# Elektroskate_Teensy_20141205.net
KiCad netlist of a schematic drawn in EAGLE
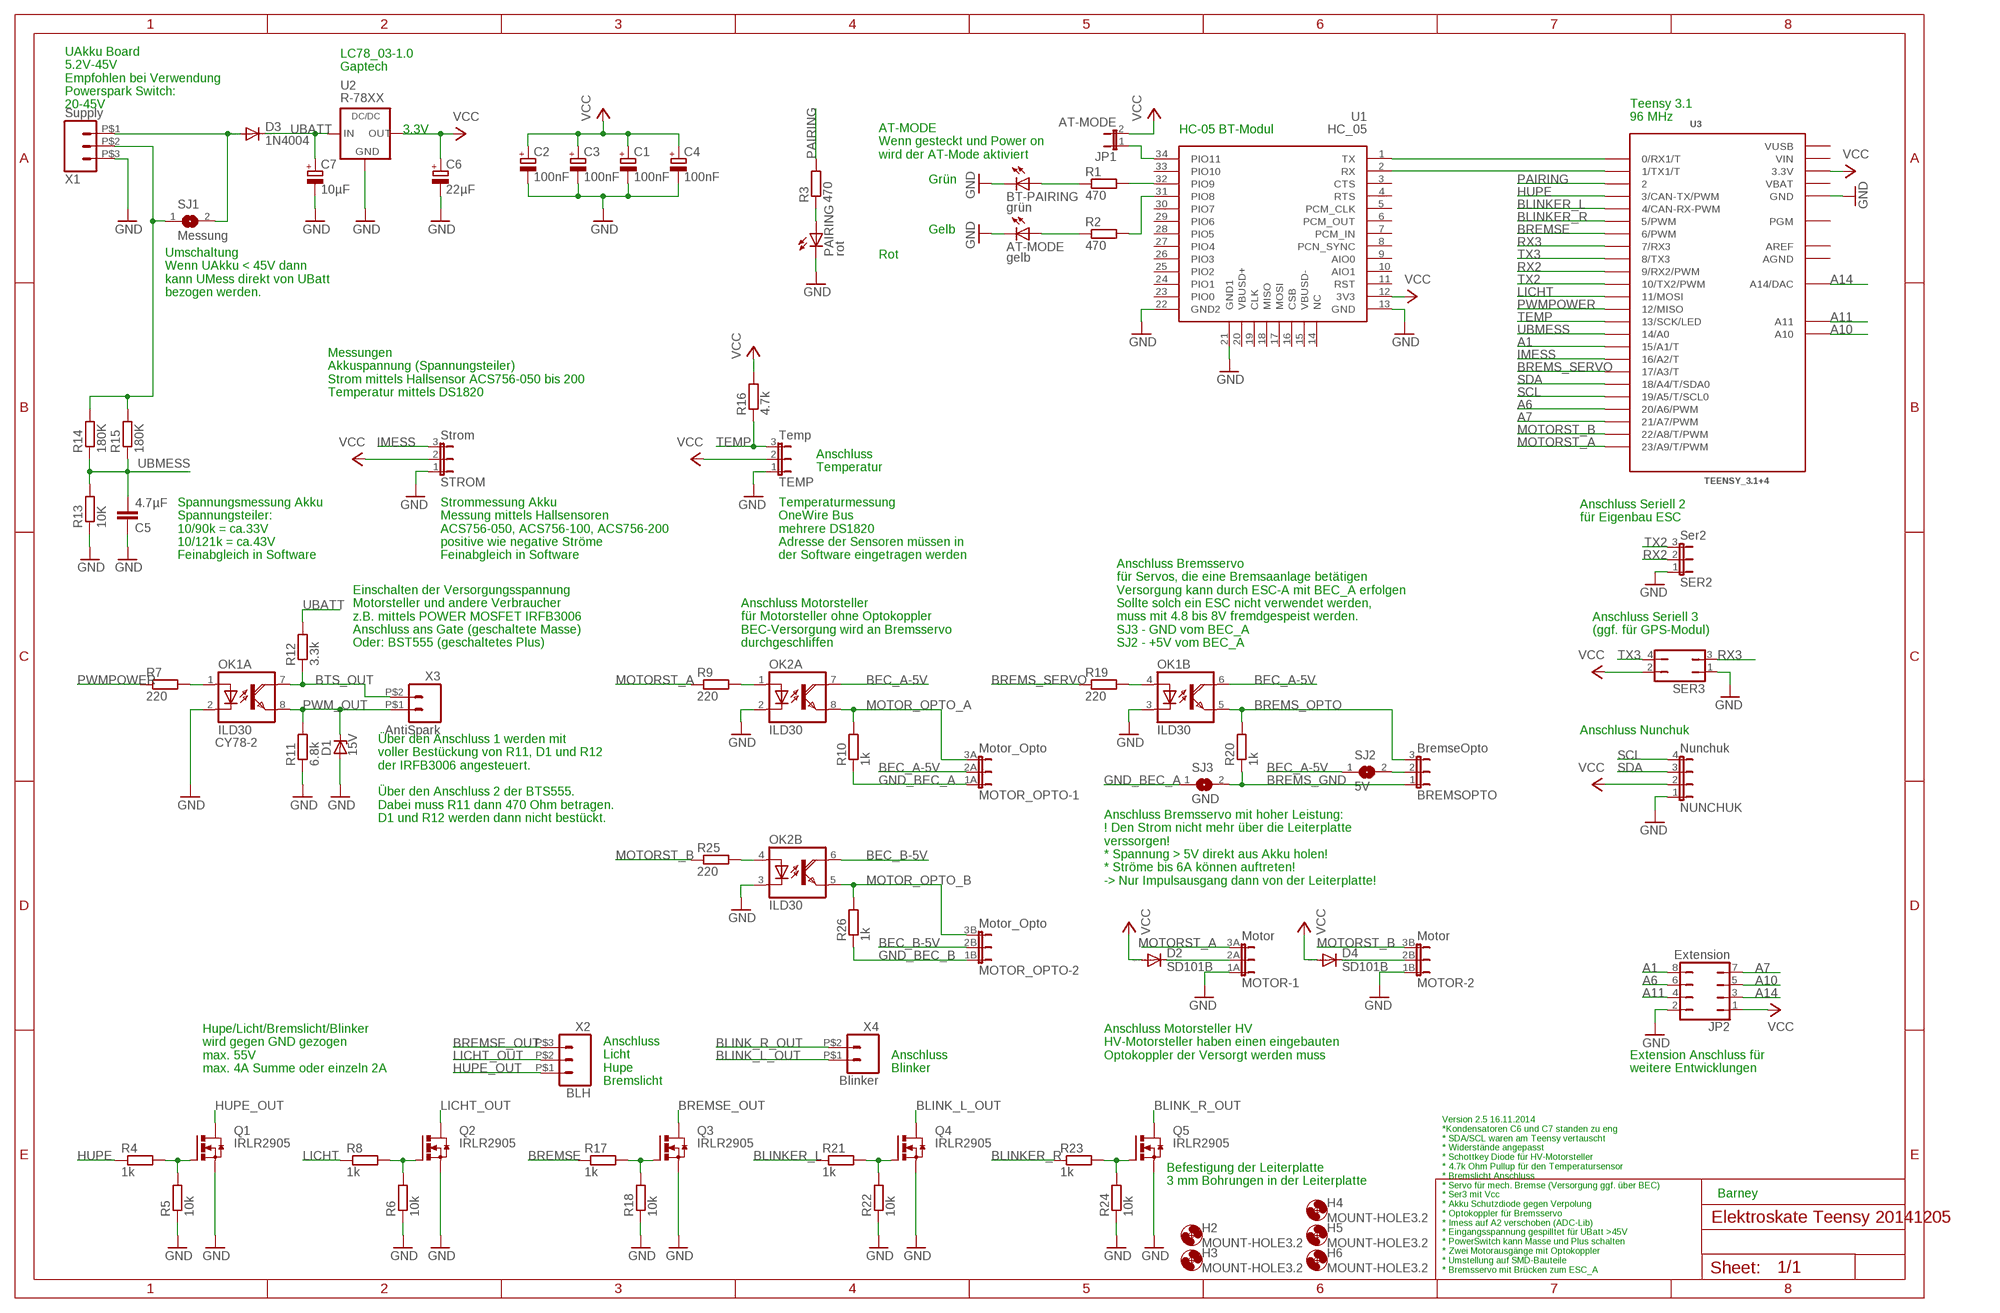
[diagram p0: schematic, sheet 1]

(export (version "E")
  (design (tool "Eeschema 10.0.6"))
  (components
    (comp (ref "AT-MODE")
      (value "gelb")
      (footprint "eagle-import:SML0805")
      (libsource (lib "eagle-import") (part "LEDSML0805"))
    )
    (comp (ref "BREMSOPTO")
      (value "BremseOpto")
      (footprint "eagle-import:JP2")
      (libsource (lib "eagle-import") (part "JP2E"))
    )
    (comp (ref "BT-PAIRING")
      (value "grün")
      (footprint "eagle-import:SML0805")
      (libsource (lib "eagle-import") (part "LEDSML0805"))
    )
    (comp (ref "C1")
      (value "100nF")
      (footprint "eagle-import:B45181A")
      (libsource (lib "eagle-import") (part "CPOL-EUB45181A"))
    )
    (comp (ref "C2")
      (value "100nF")
      (footprint "eagle-import:B45181A")
      (libsource (lib "eagle-import") (part "CPOL-EUB45181A"))
    )
    (comp (ref "C3")
      (value "100nF")
      (footprint "eagle-import:B45181A")
      (libsource (lib "eagle-import") (part "CPOL-EUB45181A"))
    )
    (comp (ref "C4")
      (value "100nF")
      (footprint "eagle-import:B45181A")
      (libsource (lib "eagle-import") (part "CPOL-EUB45181A"))
    )
    (comp (ref "C5")
      (value "4.7µF")
      (footprint "eagle-import:C1206")
      (libsource (lib "eagle-import") (part "C-EUC1206"))
    )
    (comp (ref "C6")
      (value "22µF")
      (footprint "eagle-import:UD-4X5,8_NICHICON")
      (libsource (lib "eagle-import") (part "CPOL-EUUD-4X5,8"))
    )
    (comp (ref "C7")
      (value "10µF")
      (footprint "eagle-import:UD-6,3X5,8_NICHICON")
      (libsource (lib "eagle-import") (part "CPOL-EUUD-6,3X8,8"))
    )
    (comp (ref "D1")
      (value "15V")
      (footprint "eagle-import:DO35Z10")
      (libsource (lib "eagle-import") (part "ZPD"))
    )
    (comp (ref "D2")
      (value "SD101B")
      (footprint "eagle-import:SOD123")
      (libsource (lib "eagle-import") (part "MBR0520LT"))
    )
    (comp (ref "D3")
      (value "1N4004")
      (footprint "eagle-import:DO41-10")
      (libsource (lib "eagle-import") (part "1N4004"))
    )
    (comp (ref "D4")
      (value "SD101B")
      (footprint "eagle-import:SOD123")
      (libsource (lib "eagle-import") (part "MBR0520LT"))
    )
    (comp (ref "H2")
      (value "MOUNT-HOLE3.2")
      (footprint "eagle-import:3,2")
      (libsource (lib "eagle-import") (part "MOUNT-HOLE3.2"))
    )
    (comp (ref "H3")
      (value "MOUNT-HOLE3.2")
      (footprint "eagle-import:3,2")
      (libsource (lib "eagle-import") (part "MOUNT-HOLE3.2"))
    )
    (comp (ref "H4")
      (value "MOUNT-HOLE3.2")
      (footprint "eagle-import:3,2")
      (libsource (lib "eagle-import") (part "MOUNT-HOLE3.2"))
    )
    (comp (ref "H5")
      (value "MOUNT-HOLE3.2")
      (footprint "eagle-import:3,2")
      (libsource (lib "eagle-import") (part "MOUNT-HOLE3.2"))
    )
    (comp (ref "H6")
      (value "MOUNT-HOLE3.2")
      (footprint "eagle-import:3,2")
      (libsource (lib "eagle-import") (part "MOUNT-HOLE3.2"))
    )
    (comp (ref "JP1")
      (value "AT-MODE")
      (footprint "eagle-import:JP1")
      (libsource (lib "eagle-import") (part "JP1E"))
    )
    (comp (ref "JP2")
      (value "Extension")
      (footprint "eagle-import:JP4Q")
      (libsource (lib "eagle-import") (part "JP4Q"))
    )
    (comp (ref "MOTOR")
      (value "Motor")
      (footprint "eagle-import:JP3Q")
      (libsource (lib "eagle-import") (part "JP3QE"))
    )
    (comp (ref "MOTOR_OPTO")
      (value "Motor_Opto")
      (footprint "eagle-import:JP3Q")
      (libsource (lib "eagle-import") (part "JP3QE"))
    )
    (comp (ref "NUNCHUK")
      (value "Nunchuk")
      (footprint "eagle-import:JP4")
      (libsource (lib "eagle-import") (part "JP4E"))
    )
    (comp (ref "OK1")
      (value "ILD30")
      (footprint "eagle-import:DIL08")
      (fields (field (name "MF") "VISHAY/TELEFUNKEN"))
      (libsource (lib "eagle-import") (part "ILD30"))
    )
    (comp (ref "OK2")
      (value "ILD30")
      (footprint "eagle-import:DIL08")
      (fields (field (name "MF") "VISHAY/TELEFUNKEN"))
      (libsource (lib "eagle-import") (part "ILD30"))
    )
    (comp (ref "PAIRING")
      (value "rot")
      (footprint "eagle-import:SML0805")
      (libsource (lib "eagle-import") (part "LEDSML0805"))
    )
    (comp (ref "Q1")
      (value "IRLR2905")
      (footprint "eagle-import:D-PAK_TO252AA")
      (libsource (lib "eagle-import") (part "IRLR2905"))
    )
    (comp (ref "Q2")
      (value "IRLR2905")
      (footprint "eagle-import:D-PAK_TO252AA")
      (libsource (lib "eagle-import") (part "IRLR2905"))
    )
    (comp (ref "Q3")
      (value "IRLR2905")
      (footprint "eagle-import:D-PAK_TO252AA")
      (libsource (lib "eagle-import") (part "IRLR2905"))
    )
    (comp (ref "Q4")
      (value "IRLR2905")
      (footprint "eagle-import:D-PAK_TO252AA")
      (libsource (lib "eagle-import") (part "IRLR2905"))
    )
    (comp (ref "Q5")
      (value "IRLR2905")
      (footprint "eagle-import:D-PAK_TO252AA")
      (libsource (lib "eagle-import") (part "IRLR2905"))
    )
    (comp (ref "R1")
      (value "470")
      (footprint "eagle-import:R1206")
      (libsource (lib "eagle-import") (part "R-EU_R1206"))
    )
    (comp (ref "R2")
      (value "470")
      (footprint "eagle-import:R1206")
      (libsource (lib "eagle-import") (part "R-EU_R1206"))
    )
    (comp (ref "R3")
      (value "470")
      (footprint "eagle-import:R1206")
      (libsource (lib "eagle-import") (part "R-EU_R1206"))
    )
    (comp (ref "R4")
      (value "1k")
      (footprint "eagle-import:R1206")
      (libsource (lib "eagle-import") (part "R-EU_R1206"))
    )
    (comp (ref "R5")
      (value "10k")
      (footprint "eagle-import:R1206")
      (libsource (lib "eagle-import") (part "R-EU_R1206"))
    )
    (comp (ref "R6")
      (value "10k")
      (footprint "eagle-import:R1206")
      (libsource (lib "eagle-import") (part "R-EU_R1206"))
    )
    (comp (ref "R7")
      (value "220")
      (footprint "eagle-import:R1206")
      (libsource (lib "eagle-import") (part "R-EU_R1206"))
    )
    (comp (ref "R8")
      (value "1k")
      (footprint "eagle-import:R1206")
      (libsource (lib "eagle-import") (part "R-EU_R1206"))
    )
    (comp (ref "R9")
      (value "220")
      (footprint "eagle-import:R1206")
      (libsource (lib "eagle-import") (part "R-EU_R1206"))
    )
    (comp (ref "R10")
      (value "1k")
      (footprint "eagle-import:R1206")
      (libsource (lib "eagle-import") (part "R-EU_R1206"))
    )
    (comp (ref "R11")
      (value "6.8k")
      (footprint "eagle-import:R1206")
      (libsource (lib "eagle-import") (part "R-EU_R1206"))
    )
    (comp (ref "R12")
      (value "3.3k")
      (footprint "eagle-import:R1206")
      (libsource (lib "eagle-import") (part "R-EU_R1206"))
    )
    (comp (ref "R13")
      (value "10K")
      (footprint "eagle-import:R1206")
      (libsource (lib "eagle-import") (part "R-EU_R1206"))
    )
    (comp (ref "R14")
      (value "180K")
      (footprint "eagle-import:R1206")
      (libsource (lib "eagle-import") (part "R-EU_R1206"))
    )
    (comp (ref "R15")
      (value "180K")
      (footprint "eagle-import:R1206")
      (libsource (lib "eagle-import") (part "R-EU_R1206"))
    )
    (comp (ref "R16")
      (value "4.7k")
      (footprint "eagle-import:R1206")
      (libsource (lib "eagle-import") (part "R-EU_R1206"))
    )
    (comp (ref "R17")
      (value "1k")
      (footprint "eagle-import:R1206")
      (libsource (lib "eagle-import") (part "R-EU_R1206"))
    )
    (comp (ref "R18")
      (value "10k")
      (footprint "eagle-import:R1206")
      (libsource (lib "eagle-import") (part "R-EU_R1206"))
    )
    (comp (ref "R19")
      (value "220")
      (footprint "eagle-import:R1206")
      (libsource (lib "eagle-import") (part "R-EU_R1206"))
    )
    (comp (ref "R20")
      (value "1k")
      (footprint "eagle-import:R1206")
      (libsource (lib "eagle-import") (part "R-EU_R1206"))
    )
    (comp (ref "R21")
      (value "1k")
      (footprint "eagle-import:R1206")
      (libsource (lib "eagle-import") (part "R-EU_R1206"))
    )
    (comp (ref "R22")
      (value "10k")
      (footprint "eagle-import:R1206")
      (libsource (lib "eagle-import") (part "R-EU_R1206"))
    )
    (comp (ref "R23")
      (value "1k")
      (footprint "eagle-import:R1206")
      (libsource (lib "eagle-import") (part "R-EU_R1206"))
    )
    (comp (ref "R24")
      (value "10k")
      (footprint "eagle-import:R1206")
      (libsource (lib "eagle-import") (part "R-EU_R1206"))
    )
    (comp (ref "R25")
      (value "220")
      (footprint "eagle-import:R1206")
      (libsource (lib "eagle-import") (part "R-EU_R1206"))
    )
    (comp (ref "R26")
      (value "1k")
      (footprint "eagle-import:R1206")
      (libsource (lib "eagle-import") (part "R-EU_R1206"))
    )
    (comp (ref "SER2")
      (value "Ser2")
      (footprint "eagle-import:JP2")
      (libsource (lib "eagle-import") (part "JP2E"))
    )
    (comp (ref "SER3")
      (value "JP2Q")
      (footprint "eagle-import:JP2Q")
      (libsource (lib "eagle-import") (part "JP2Q"))
    )
    (comp (ref "SJ1")
      (value "Messung")
      (footprint "eagle-import:SJ")
      (libsource (lib "eagle-import") (part "SJ"))
    )
    (comp (ref "SJ2") (value "5V") (footprint "eagle-import:SJ") (libsource (lib "eagle-import") (part "SJ")))
    (comp (ref "SJ3")
      (value "GND")
      (footprint "eagle-import:SJ")
      (libsource (lib "eagle-import") (part "SJ"))
    )
    (comp (ref "STROM")
      (value "Strom")
      (footprint "eagle-import:JP2")
      (libsource (lib "eagle-import") (part "JP2E"))
    )
    (comp (ref "TEMP")
      (value "Temp")
      (footprint "eagle-import:JP2")
      (libsource (lib "eagle-import") (part "JP2E"))
    )
    (comp (ref "U1")
      (value "HC_05")
      (footprint "eagle-import:BLUETOOTH_SMD")
      (libsource (lib "eagle-import") (part "HC_05"))
    )
    (comp (ref "U2")
      (value "R-78XX")
      (footprint "eagle-import:R-78XX")
      (fields (field (name "SPANNUNG") "3.3V"))
      (libsource (lib "eagle-import") (part "R-78XX"))
    )
    (comp (ref "U3")
      (value "TEENSY_3.1+4")
      (footprint "eagle-import:TEENSY_3.1+4")
      (libsource (lib "eagle-import") (part "TEENSY_3.1+4"))
    )
    (comp (ref "X1")
      (value "Supply")
      (footprint "eagle-import:03W")
      (libsource (lib "eagle-import") (part "PSS254_3GEWINKELT"))
    )
    (comp (ref "X2")
      (value "BLH")
      (footprint "eagle-import:03W")
      (libsource (lib "eagle-import") (part "PSS254_3GEWINKELT"))
    )
    (comp (ref "X3")
      (value "AntiSpark")
      (footprint "eagle-import:02W")
      (libsource (lib "eagle-import") (part "PSS254_2GEWINKELT"))
    )
    (comp (ref "X4")
      (value "Blinker")
      (footprint "eagle-import:02W")
      (libsource (lib "eagle-import") (part "PSS254_2GEWINKELT"))
    )
  )
  (nets
    (net (code "1") (name "/A1") (class "Default")
      (node (ref "JP2") (pin "8") (pinfunction "8_8") (pintype "passive"))
      (node (ref "U3") (pin "15/A1") (pinfunction "15/A1/T_15/A1") (pintype "bidirectional"))
    )
    (net (code "2") (name "/A6") (class "Default")
      (node (ref "JP2") (pin "6") (pinfunction "6_6") (pintype "passive"))
      (node (ref "U3") (pin "20/A6") (pinfunction "20/A6/PWM_20/A6") (pintype "bidirectional"))
    )
    (net (code "3") (name "/A7") (class "Default")
      (node (ref "JP2") (pin "7") (pinfunction "7_7") (pintype "passive"))
      (node (ref "U3") (pin "21/A7") (pinfunction "21/A7/PWM_21/A7") (pintype "bidirectional"))
    )
    (net (code "4") (name "/A10") (class "Default")
      (node (ref "JP2") (pin "5") (pinfunction "5_5") (pintype "passive"))
      (node (ref "U3") (pin "A10") (pinfunction "A10_A10") (pintype "bidirectional"))
    )
    (net (code "5") (name "/A11") (class "Default")
      (node (ref "JP2") (pin "4") (pinfunction "4_4") (pintype "passive"))
      (node (ref "U3") (pin "A11") (pinfunction "A11_A11") (pintype "bidirectional"))
    )
    (net (code "6") (name "/A14") (class "Default")
      (node (ref "JP2") (pin "3") (pinfunction "3_3") (pintype "passive"))
      (node (ref "U3") (pin "A14") (pinfunction "A14/DAC_A14") (pintype "bidirectional"))
    )
    (net (code "7") (name "/AGND") (class "Default")
      (node (ref "U3") (pin "AGND") (pinfunction "AGND_AGND") (pintype "power_in"))
    )
    (net (code "8") (name "/AREF") (class "Default")
      (node (ref "U3") (pin "AREF") (pinfunction "AREF_AREF") (pintype "power_in"))
    )
    (net (code "9") (name "/BEC_A-5V") (class "Default")
      (node (ref "MOTOR_OPTO") (pin "2A") (pinfunction "2_2A") (pintype "passive"))
      (node (ref "OK1") (pin "6") (pinfunction "COL_6") (pintype "passive"))
      (node (ref "OK2") (pin "7") (pinfunction "COL_7") (pintype "passive"))
      (node (ref "SJ2") (pin "1") (pinfunction "1_1") (pintype "passive"))
    )
    (net (code "10") (name "/BEC_B-5V") (class "Default")
      (node (ref "MOTOR_OPTO") (pin "2B") (pinfunction "2_2B") (pintype "passive"))
      (node (ref "OK2") (pin "6") (pinfunction "COL_6") (pintype "passive"))
    )
    (net (code "11") (name "/BLINKER_L") (class "Default")
      (node (ref "R21") (pin "1") (pinfunction "1_1") (pintype "passive"))
      (node (ref "U3") (pin "4") (pinfunction "4/CAN-RX-PWM_4") (pintype "bidirectional"))
    )
    (net (code "12") (name "/BLINKER_R") (class "Default")
      (node (ref "R23") (pin "1") (pinfunction "1_1") (pintype "passive"))
      (node (ref "U3") (pin "5") (pinfunction "5/PWM_5") (pintype "bidirectional"))
    )
    (net (code "13") (name "/BLINK_L_OUT") (class "Default")
      (node (ref "Q4") (pin "4") (pinfunction "D_4") (pintype "passive"))
      (node (ref "X4") (pin "P$1") (pinfunction "1_P$1") (pintype "passive"))
    )
    (net (code "14") (name "/BLINK_R_OUT") (class "Default")
      (node (ref "Q5") (pin "4") (pinfunction "D_4") (pintype "passive"))
      (node (ref "X4") (pin "P$2") (pinfunction "2_P$2") (pintype "passive"))
    )
    (net (code "15") (name "/BREMSE") (class "Default")
      (node (ref "R17") (pin "1") (pinfunction "1_1") (pintype "passive"))
      (node (ref "U3") (pin "6") (pinfunction "6/PWM_6") (pintype "bidirectional"))
    )
    (net (code "16") (name "/BREMSE_OUT") (class "Default")
      (node (ref "Q3") (pin "4") (pinfunction "D_4") (pintype "passive"))
      (node (ref "X2") (pin "P$3") (pinfunction "3_P$3") (pintype "passive"))
    )
    (net (code "17") (name "/BREMS_GND") (class "Default")
      (node (ref "BREMSOPTO") (pin "1") (pinfunction "1_1") (pintype "passive"))
      (node (ref "R20") (pin "1") (pinfunction "1_1") (pintype "passive"))
      (node (ref "SJ3") (pin "2") (pinfunction "2_2") (pintype "passive"))
    )
    (net (code "18") (name "/BREMS_OPTO") (class "Default")
      (node (ref "BREMSOPTO") (pin "3") (pinfunction "3_3") (pintype "passive"))
      (node (ref "OK1") (pin "5") (pinfunction "EMI_5") (pintype "passive"))
      (node (ref "R20") (pin "2") (pinfunction "2_2") (pintype "passive"))
    )
    (net (code "19") (name "/BREMS_SERVO") (class "Default")
      (node (ref "R19") (pin "1") (pinfunction "1_1") (pintype "passive"))
      (node (ref "U3") (pin "17/A3") (pinfunction "17/A3/T_17/A3") (pintype "bidirectional"))
    )
    (net (code "20") (name "/BTS_OUT") (class "Default")
      (node (ref "OK1") (pin "7") (pinfunction "COL_7") (pintype "passive"))
      (node (ref "R12") (pin "1") (pinfunction "1_1") (pintype "passive"))
      (node (ref "X3") (pin "P$2") (pinfunction "2_P$2") (pintype "passive"))
    )
    (net (code "21") (name "/GND_BEC_A") (class "Default")
      (node (ref "MOTOR_OPTO") (pin "1A") (pinfunction "1_1A") (pintype "passive"))
      (node (ref "R10") (pin "1") (pinfunction "1_1") (pintype "passive"))
      (node (ref "SJ3") (pin "1") (pinfunction "1_1") (pintype "passive"))
    )
    (net (code "22") (name "/GND_BEC_B") (class "Default")
      (node (ref "MOTOR_OPTO") (pin "1B") (pinfunction "1_1B") (pintype "passive"))
      (node (ref "R26") (pin "1") (pinfunction "1_1") (pintype "passive"))
    )
    (net (code "23") (name "/HUPE") (class "Default")
      (node (ref "R4") (pin "1") (pinfunction "1_1") (pintype "passive"))
      (node (ref "U3") (pin "3") (pinfunction "3/CAN-TX/PWM_3") (pintype "bidirectional"))
    )
    (net (code "24") (name "/HUPE_OUT") (class "Default")
      (node (ref "Q1") (pin "4") (pinfunction "D_4") (pintype "passive"))
      (node (ref "X2") (pin "P$1") (pinfunction "1_P$1") (pintype "passive"))
    )
    (net (code "25") (name "/IMESS") (class "Default")
      (node (ref "STROM") (pin "3") (pinfunction "3_3") (pintype "passive"))
      (node (ref "U3") (pin "16/A2") (pinfunction "16/A2/T_16/A2") (pintype "bidirectional"))
    )
    (net (code "26") (name "/LICHT") (class "Default")
      (node (ref "R8") (pin "1") (pinfunction "1_1") (pintype "passive"))
      (node (ref "U3") (pin "11") (pinfunction "11/MOSI_11") (pintype "bidirectional"))
    )
    (net (code "27") (name "/LICHT_OUT") (class "Default")
      (node (ref "Q2") (pin "4") (pinfunction "D_4") (pintype "passive"))
      (node (ref "X2") (pin "P$2") (pinfunction "2_P$2") (pintype "passive"))
    )
    (net (code "28") (name "/MOTORST_A") (class "Default")
      (node (ref "MOTOR") (pin "3A") (pinfunction "3_3A") (pintype "passive"))
      (node (ref "R9") (pin "1") (pinfunction "1_1") (pintype "passive"))
      (node (ref "U3") (pin "23/A9") (pinfunction "23/A9/T/PWM_23/A9") (pintype "bidirectional"))
    )
    (net (code "29") (name "/MOTORST_B") (class "Default")
      (node (ref "MOTOR") (pin "3B") (pinfunction "3_3B") (pintype "passive"))
      (node (ref "R25") (pin "1") (pinfunction "1_1") (pintype "passive"))
      (node (ref "U3") (pin "22/A8") (pinfunction "22/A8/T/PWM_22/A8") (pintype "bidirectional"))
    )
    (net (code "30") (name "/MOTOR_OPTO_A") (class "Default")
      (node (ref "MOTOR_OPTO") (pin "3A") (pinfunction "3_3A") (pintype "passive"))
      (node (ref "OK2") (pin "8") (pinfunction "EMI_8") (pintype "passive"))
      (node (ref "R10") (pin "2") (pinfunction "2_2") (pintype "passive"))
    )
    (net (code "31") (name "/MOTOR_OPTO_B") (class "Default")
      (node (ref "MOTOR_OPTO") (pin "3B") (pinfunction "3_3B") (pintype "passive"))
      (node (ref "OK2") (pin "5") (pinfunction "EMI_5") (pintype "passive"))
      (node (ref "R26") (pin "2") (pinfunction "2_2") (pintype "passive"))
    )
    (net (code "32") (name "/PAIRING") (class "Default")
      (node (ref "R3") (pin "2") (pinfunction "2_2") (pintype "passive"))
      (node (ref "U3") (pin "2") (pinfunction "2_2") (pintype "bidirectional"))
    )
    (net (code "33") (name "/PWMPOWER") (class "Default")
      (node (ref "R7") (pin "1") (pinfunction "1_1") (pintype "passive"))
      (node (ref "U3") (pin "12") (pinfunction "12/MISO_12") (pintype "bidirectional"))
    )
    (net (code "34") (name "/PWM_OUT") (class "Default")
      (node (ref "D1") (pin "C") (pinfunction "C_C") (pintype "passive"))
      (node (ref "OK1") (pin "8") (pinfunction "EMI_8") (pintype "passive"))
      (node (ref "R11") (pin "2") (pinfunction "2_2") (pintype "passive"))
      (node (ref "X3") (pin "P$1") (pinfunction "1_P$1") (pintype "passive"))
    )
    (net (code "35") (name "/RX2") (class "Default")
      (node (ref "SER2") (pin "2") (pinfunction "2_2") (pintype "passive"))
      (node (ref "U3") (pin "9") (pinfunction "9/RX2/PWM_9") (pintype "bidirectional"))
    )
    (net (code "36") (name "/RX3") (class "Default")
      (node (ref "SER3") (pin "3") (pinfunction "3_3") (pintype "passive"))
      (node (ref "U3") (pin "7") (pinfunction "7/RX3_7") (pintype "bidirectional"))
    )
    (net (code "37") (name "/SCL") (class "Default")
      (node (ref "NUNCHUK") (pin "4") (pinfunction "4_4") (pintype "passive"))
      (node (ref "U3") (pin "19/A5") (pinfunction "19/A5/T/SCL0_19/A5") (pintype "bidirectional"))
    )
    (net (code "38") (name "/SDA") (class "Default")
      (node (ref "NUNCHUK") (pin "3") (pinfunction "3_3") (pintype "passive"))
      (node (ref "U3") (pin "18/A4") (pinfunction "18/A4/T/SDA0_18/A4") (pintype "bidirectional"))
    )
    (net (code "39") (name "/TEMP") (class "Default")
      (node (ref "R16") (pin "1") (pinfunction "1_1") (pintype "passive"))
      (node (ref "TEMP") (pin "3") (pinfunction "3_3") (pintype "passive"))
      (node (ref "U3") (pin "13") (pinfunction "13/SCK/LED_13") (pintype "bidirectional"))
    )
    (net (code "40") (name "/TX2") (class "Default")
      (node (ref "SER2") (pin "3") (pinfunction "3_3") (pintype "passive"))
      (node (ref "U3") (pin "10") (pinfunction "10/TX2/PWM_10") (pintype "bidirectional"))
    )
    (net (code "41") (name "/TX3") (class "Default")
      (node (ref "SER3") (pin "4") (pinfunction "4_4") (pintype "passive"))
      (node (ref "U3") (pin "8") (pinfunction "8/TX3_8") (pintype "bidirectional"))
    )
    (net (code "42") (name "/UBATT") (class "Default")
      (node (ref "C7") (pin "+") (pinfunction "+_+") (pintype "passive"))
      (node (ref "D3") (pin "C") (pinfunction "C_C") (pintype "passive"))
      (node (ref "R12") (pin "2") (pinfunction "2_2") (pintype "passive"))
      (node (ref "U2") (pin "1") (pinfunction "IN_1") (pintype "input"))
    )
    (net (code "43") (name "/UBMESS") (class "Default")
      (node (ref "C5") (pin "2") (pinfunction "2_2") (pintype "passive"))
      (node (ref "R13") (pin "2") (pinfunction "2_2") (pintype "passive"))
      (node (ref "R14") (pin "1") (pinfunction "1_1") (pintype "passive"))
      (node (ref "R15") (pin "1") (pinfunction "1_1") (pintype "passive"))
      (node (ref "U3") (pin "14/A0") (pinfunction "14/A0_14/A0") (pintype "bidirectional"))
    )
    (net (code "44") (name "/VBAT") (class "Default")
      (node (ref "U3") (pin "VBAT") (pinfunction "VBAT_VBAT") (pintype "power_in"))
    )
    (net (code "45") (name "/VIN") (class "Default")
      (node (ref "U3") (pin "VIN") (pinfunction "VIN_VIN") (pintype "power_in"))
    )
    (net (code "46") (name "/VUSB") (class "Default")
      (node (ref "U3") (pin "VUSB") (pinfunction "VUSB_VUSB") (pintype "power_in"))
    )
    (net (code "47") (name "GND") (class "Default")
      (node (ref "AT-MODE") (pin "C") (pinfunction "C_C") (pintype "passive"))
      (node (ref "BT-PAIRING") (pin "C") (pinfunction "C_C") (pintype "passive"))
      (node (ref "C1") (pin "-") (pinfunction "-_-") (pintype "passive"))
      (node (ref "C2") (pin "-") (pinfunction "-_-") (pintype "passive"))
      (node (ref "C3") (pin "-") (pinfunction "-_-") (pintype "passive"))
      (node (ref "C4") (pin "-") (pinfunction "-_-") (pintype "passive"))
      (node (ref "C5") (pin "1") (pinfunction "1_1") (pintype "passive"))
      (node (ref "C6") (pin "-") (pinfunction "-_-") (pintype "passive"))
      (node (ref "C7") (pin "-") (pinfunction "-_-") (pintype "passive"))
      (node (ref "D1") (pin "A") (pinfunction "A_A") (pintype "passive"))
      (node (ref "JP2") (pin "2") (pinfunction "2_2") (pintype "passive"))
      (node (ref "MOTOR") (pin "1A") (pinfunction "1_1A") (pintype "passive"))
      (node (ref "MOTOR") (pin "1B") (pinfunction "1_1B") (pintype "passive"))
      (node (ref "NUNCHUK") (pin "1") (pinfunction "1_1") (pintype "passive"))
      (node (ref "OK1") (pin "2") (pinfunction "C_2") (pintype "passive"))
      (node (ref "OK1") (pin "3") (pinfunction "C_3") (pintype "passive"))
      (node (ref "OK2") (pin "2") (pinfunction "C_2") (pintype "passive"))
      (node (ref "OK2") (pin "3") (pinfunction "C_3") (pintype "passive"))
      (node (ref "PAIRING") (pin "C") (pinfunction "C_C") (pintype "passive"))
      (node (ref "Q1") (pin "3") (pinfunction "S_3") (pintype "passive"))
      (node (ref "Q2") (pin "3") (pinfunction "S_3") (pintype "passive"))
      (node (ref "Q3") (pin "3") (pinfunction "S_3") (pintype "passive"))
      (node (ref "Q4") (pin "3") (pinfunction "S_3") (pintype "passive"))
      (node (ref "Q5") (pin "3") (pinfunction "S_3") (pintype "passive"))
      (node (ref "R11") (pin "1") (pinfunction "1_1") (pintype "passive"))
      (node (ref "R13") (pin "1") (pinfunction "1_1") (pintype "passive"))
      (node (ref "R18") (pin "1") (pinfunction "1_1") (pintype "passive"))
      (node (ref "R22") (pin "1") (pinfunction "1_1") (pintype "passive"))
      (node (ref "R24") (pin "1") (pinfunction "1_1") (pintype "passive"))
      (node (ref "R5") (pin "1") (pinfunction "1_1") (pintype "passive"))
      (node (ref "R6") (pin "1") (pinfunction "1_1") (pintype "passive"))
      (node (ref "SER2") (pin "1") (pinfunction "1_1") (pintype "passive"))
      (node (ref "SER3") (pin "1") (pinfunction "1_1") (pintype "passive"))
      (node (ref "STROM") (pin "1") (pinfunction "1_1") (pintype "passive"))
      (node (ref "TEMP") (pin "1") (pinfunction "1_1") (pintype "passive"))
      (node (ref "U1") (pin "13") (pinfunction "GND_13") (pintype "bidirectional"))
      (node (ref "U1") (pin "21") (pinfunction "GND1_21") (pintype "bidirectional"))
      (node (ref "U1") (pin "22") (pinfunction "GND2_22") (pintype "bidirectional"))
      (node (ref "U2") (pin "2") (pinfunction "GND_2") (pintype "input"))
      (node (ref "U3") (pin "GND") (pinfunction "GND_GND") (pintype "power_in"))
      (node (ref "U3") (pin "GND1") (pinfunction "GND_GND1") (pintype "power_in"))
      (node (ref "X1") (pin "P$3") (pinfunction "3_P$3") (pintype "passive"))
    )
    (net (code "48") (name "Net-(AT-MODE-PadA)") (class "Default")
      (node (ref "AT-MODE") (pin "A") (pinfunction "A_A") (pintype "passive"))
      (node (ref "R2") (pin "1") (pinfunction "1_1") (pintype "passive"))
    )
    (net (code "49") (name "Net-(BREMSOPTO-Pad2)") (class "Default")
      (node (ref "BREMSOPTO") (pin "2") (pinfunction "2_2") (pintype "passive"))
      (node (ref "SJ2") (pin "2") (pinfunction "2_2") (pintype "passive"))
    )
    (net (code "50") (name "Net-(BT-PAIRING-PadA)") (class "Default")
      (node (ref "BT-PAIRING") (pin "A") (pinfunction "A_A") (pintype "passive"))
      (node (ref "R1") (pin "1") (pinfunction "1_1") (pintype "passive"))
    )
    (net (code "51") (name "Net-(MOTORA-2)") (class "Default")
      (node (ref "D2") (pin "C") (pinfunction "C_C") (pintype "passive"))
      (node (ref "MOTOR") (pin "2A") (pinfunction "2_2A") (pintype "passive"))
    )
    (net (code "52") (name "Net-(MOTORB-2)") (class "Default")
      (node (ref "D4") (pin "C") (pinfunction "C_C") (pintype "passive"))
      (node (ref "MOTOR") (pin "2B") (pinfunction "2_2B") (pintype "passive"))
    )
    (net (code "53") (name "Net-(OK1A-A)") (class "Default")
      (node (ref "OK1") (pin "1") (pinfunction "A_1") (pintype "passive"))
      (node (ref "R7") (pin "2") (pinfunction "2_2") (pintype "passive"))
    )
    (net (code "54") (name "Net-(OK1B-A)") (class "Default")
      (node (ref "OK1") (pin "4") (pinfunction "A_4") (pintype "passive"))
      (node (ref "R19") (pin "2") (pinfunction "2_2") (pintype "passive"))
    )
    (net (code "55") (name "Net-(OK2A-A)") (class "Default")
      (node (ref "OK2") (pin "1") (pinfunction "A_1") (pintype "passive"))
      (node (ref "R9") (pin "2") (pinfunction "2_2") (pintype "passive"))
    )
    (net (code "56") (name "Net-(OK2B-A)") (class "Default")
      (node (ref "OK2") (pin "4") (pinfunction "A_4") (pintype "passive"))
      (node (ref "R25") (pin "2") (pinfunction "2_2") (pintype "passive"))
    )
    (net (code "57") (name "Net-(PAIRING-PadA)") (class "Default")
      (node (ref "PAIRING") (pin "A") (pinfunction "A_A") (pintype "passive"))
      (node (ref "R3") (pin "1") (pinfunction "1_1") (pintype "passive"))
    )
    (net (code "58") (name "Net-(Q1-G)") (class "Default")
      (node (ref "Q1") (pin "1") (pinfunction "G_1") (pintype "passive"))
      (node (ref "R4") (pin "2") (pinfunction "2_2") (pintype "passive"))
      (node (ref "R5") (pin "2") (pinfunction "2_2") (pintype "passive"))
    )
    (net (code "59") (name "Net-(Q2-G)") (class "Default")
      (node (ref "Q2") (pin "1") (pinfunction "G_1") (pintype "passive"))
      (node (ref "R6") (pin "2") (pinfunction "2_2") (pintype "passive"))
      (node (ref "R8") (pin "2") (pinfunction "2_2") (pintype "passive"))
    )
    (net (code "60") (name "Net-(Q3-G)") (class "Default")
      (node (ref "Q3") (pin "1") (pinfunction "G_1") (pintype "passive"))
      (node (ref "R17") (pin "2") (pinfunction "2_2") (pintype "passive"))
      (node (ref "R18") (pin "2") (pinfunction "2_2") (pintype "passive"))
    )
    (net (code "61") (name "Net-(Q4-G)") (class "Default")
      (node (ref "Q4") (pin "1") (pinfunction "G_1") (pintype "passive"))
      (node (ref "R21") (pin "2") (pinfunction "2_2") (pintype "passive"))
      (node (ref "R22") (pin "2") (pinfunction "2_2") (pintype "passive"))
    )
    (net (code "62") (name "Net-(Q5-G)") (class "Default")
      (node (ref "Q5") (pin "1") (pinfunction "G_1") (pintype "passive"))
      (node (ref "R23") (pin "2") (pinfunction "2_2") (pintype "passive"))
      (node (ref "R24") (pin "2") (pinfunction "2_2") (pintype "passive"))
    )
    (net (code "63") (name "Net-(U1-PIO8)") (class "Default")
      (node (ref "R2") (pin "2") (pinfunction "2_2") (pintype "passive"))
      (node (ref "U1") (pin "31") (pinfunction "PIO8_31") (pintype "bidirectional"))
    )
    (net (code "64") (name "Net-(U1-PIO9)") (class "Default")
      (node (ref "R1") (pin "2") (pinfunction "2_2") (pintype "passive"))
      (node (ref "U1") (pin "32") (pinfunction "PIO9_32") (pintype "bidirectional"))
    )
    (net (code "65") (name "Net-(U1-PIO11)") (class "Default")
      (node (ref "JP1") (pin "1") (pinfunction "1_1") (pintype "passive"))
      (node (ref "U1") (pin "34") (pinfunction "PIO11_34") (pintype "bidirectional"))
    )
    (net (code "66") (name "Net-(U1-RX)") (class "Default")
      (node (ref "U1") (pin "2") (pinfunction "RX_2") (pintype "bidirectional"))
      (node (ref "U3") (pin "1") (pinfunction "1/TX1/T_1") (pintype "bidirectional"))
    )
    (net (code "67") (name "Net-(U1-TX)") (class "Default")
      (node (ref "U1") (pin "1") (pinfunction "TX_1") (pintype "bidirectional"))
      (node (ref "U3") (pin "0") (pinfunction "0/RX1/T_0") (pintype "bidirectional"))
    )
    (net (code "68") (name "Net-(X1-1)") (class "Default")
      (node (ref "D3") (pin "A") (pinfunction "A_A") (pintype "passive"))
      (node (ref "SJ1") (pin "2") (pinfunction "2_2") (pintype "passive"))
      (node (ref "X1") (pin "P$1") (pinfunction "1_P$1") (pintype "passive"))
    )
    (net (code "69") (name "Net-(X1-2)") (class "Default")
      (node (ref "R14") (pin "2") (pinfunction "2_2") (pintype "passive"))
      (node (ref "R15") (pin "2") (pinfunction "2_2") (pintype "passive"))
      (node (ref "SJ1") (pin "1") (pinfunction "1_1") (pintype "passive"))
      (node (ref "X1") (pin "P$2") (pinfunction "2_P$2") (pintype "passive"))
    )
    (net (code "70") (name "VCC") (class "Default")
      (node (ref "C1") (pin "+") (pinfunction "+_+") (pintype "passive"))
      (node (ref "C2") (pin "+") (pinfunction "+_+") (pintype "passive"))
      (node (ref "C3") (pin "+") (pinfunction "+_+") (pintype "passive"))
      (node (ref "C4") (pin "+") (pinfunction "+_+") (pintype "passive"))
      (node (ref "C6") (pin "+") (pinfunction "+_+") (pintype "passive"))
      (node (ref "D2") (pin "A") (pinfunction "A_A") (pintype "passive"))
      (node (ref "D4") (pin "A") (pinfunction "A_A") (pintype "passive"))
      (node (ref "JP1") (pin "2") (pinfunction "2_2") (pintype "passive"))
      (node (ref "JP2") (pin "1") (pinfunction "1_1") (pintype "passive"))
      (node (ref "NUNCHUK") (pin "2") (pinfunction "2_2") (pintype "passive"))
      (node (ref "R16") (pin "2") (pinfunction "2_2") (pintype "passive"))
      (node (ref "SER3") (pin "2") (pinfunction "2_2") (pintype "passive"))
      (node (ref "STROM") (pin "2") (pinfunction "2_2") (pintype "passive"))
      (node (ref "TEMP") (pin "2") (pinfunction "2_2") (pintype "passive"))
      (node (ref "U1") (pin "12") (pinfunction "3V3_12") (pintype "bidirectional"))
      (node (ref "U2") (pin "3") (pinfunction "OUT_3") (pintype "passive"))
      (node (ref "U3") (pin "3.3V") (pinfunction "3.3V_3.3V") (pintype "power_in"))
      (node (ref "U3") (pin "3.3V1") (pinfunction "3.3V_3.3V1") (pintype "power_in"))
    )
    (net (code "71") (name "unconnected-(U1-AIO0-Pad9)") (class "Default")
      (node (ref "U1") (pin "9") (pinfunction "AIO0_9") (pintype "bidirectional"))
    )
    (net (code "72") (name "unconnected-(U1-AIO1-Pad10)") (class "Default")
      (node (ref "U1") (pin "10") (pinfunction "AIO1_10") (pintype "bidirectional"))
    )
    (net (code "73") (name "unconnected-(U1-CLK-Pad19)") (class "Default")
      (node (ref "U1") (pin "19") (pinfunction "CLK_19") (pintype "bidirectional"))
    )
    (net (code "74") (name "unconnected-(U1-CSB-Pad16)") (class "Default")
      (node (ref "U1") (pin "16") (pinfunction "CSB_16") (pintype "bidirectional"))
    )
    (net (code "75") (name "unconnected-(U1-CTS-Pad3)") (class "Default")
      (node (ref "U1") (pin "3") (pinfunction "CTS_3") (pintype "bidirectional"))
    )
    (net (code "76") (name "unconnected-(U1-MISO-Pad18)") (class "Default")
      (node (ref "U1") (pin "18") (pinfunction "MISO_18") (pintype "bidirectional"))
    )
    (net (code "77") (name "unconnected-(U1-MOSI-Pad17)") (class "Default")
      (node (ref "U1") (pin "17") (pinfunction "MOSI_17") (pintype "bidirectional"))
    )
    (net (code "78") (name "unconnected-(U1-NC-Pad14)") (class "Default")
      (node (ref "U1") (pin "14") (pinfunction "NC_14") (pintype "bidirectional"))
    )
    (net (code "79") (name "unconnected-(U1-PCM_CLK-Pad5)") (class "Default")
      (node (ref "U1") (pin "5") (pinfunction "PCM_CLK_5") (pintype "bidirectional"))
    )
    (net (code "80") (name "unconnected-(U1-PCM_IN-Pad7)") (class "Default")
      (node (ref "U1") (pin "7") (pinfunction "PCM_IN_7") (pintype "bidirectional"))
    )
    (net (code "81") (name "unconnected-(U1-PCM_OUT-Pad6)") (class "Default")
      (node (ref "U1") (pin "6") (pinfunction "PCM_OUT_6") (pintype "bidirectional"))
    )
    (net (code "82") (name "unconnected-(U1-PCN_SYNC-Pad8)") (class "Default")
      (node (ref "U1") (pin "8") (pinfunction "PCN_SYNC_8") (pintype "bidirectional"))
    )
    (net (code "83") (name "unconnected-(U1-PIO0-Pad23)") (class "Default")
      (node (ref "U1") (pin "23") (pinfunction "PIO0_23") (pintype "bidirectional"))
    )
    (net (code "84") (name "unconnected-(U1-PIO1-Pad24)") (class "Default")
      (node (ref "U1") (pin "24") (pinfunction "PIO1_24") (pintype "bidirectional"))
    )
    (net (code "85") (name "unconnected-(U1-PIO2-Pad25)") (class "Default")
      (node (ref "U1") (pin "25") (pinfunction "PIO2_25") (pintype "bidirectional"))
    )
    (net (code "86") (name "unconnected-(U1-PIO3-Pad26)") (class "Default")
      (node (ref "U1") (pin "26") (pinfunction "PIO3_26") (pintype "bidirectional"))
    )
    (net (code "87") (name "unconnected-(U1-PIO4-Pad27)") (class "Default")
      (node (ref "U1") (pin "27") (pinfunction "PIO4_27") (pintype "bidirectional"))
    )
    (net (code "88") (name "unconnected-(U1-PIO5-Pad28)") (class "Default")
      (node (ref "U1") (pin "28") (pinfunction "PIO5_28") (pintype "bidirectional"))
    )
    (net (code "89") (name "unconnected-(U1-PIO6-Pad29)") (class "Default")
      (node (ref "U1") (pin "29") (pinfunction "PIO6_29") (pintype "bidirectional"))
    )
    (net (code "90") (name "unconnected-(U1-PIO7-Pad30)") (class "Default")
      (node (ref "U1") (pin "30") (pinfunction "PIO7_30") (pintype "bidirectional"))
    )
    (net (code "91") (name "unconnected-(U1-PIO10-Pad33)") (class "Default")
      (node (ref "U1") (pin "33") (pinfunction "PIO10_33") (pintype "bidirectional"))
    )
    (net (code "92") (name "unconnected-(U1-RST-Pad11)") (class "Default")
      (node (ref "U1") (pin "11") (pinfunction "RST_11") (pintype "bidirectional"))
    )
    (net (code "93") (name "unconnected-(U1-RTS-Pad4)") (class "Default")
      (node (ref "U1") (pin "4") (pinfunction "RTS_4") (pintype "bidirectional"))
    )
    (net (code "94") (name "unconnected-(U1-VBUSD+-Pad20)") (class "Default")
      (node (ref "U1") (pin "20") (pinfunction "VBUSD+_20") (pintype "bidirectional"))
    )
    (net (code "95") (name "unconnected-(U1-VBUSD--Pad15)") (class "Default")
      (node (ref "U1") (pin "15") (pinfunction "VBUSD-_15") (pintype "bidirectional"))
    )
    (net (code "96") (name "unconnected-(U3-PadPGM)") (class "Default")
      (node (ref "U3") (pin "PGM") (pinfunction "PGM_PGM") (pintype "bidirectional"))
    )
  )
)
